# Config.net
KiCad netlist of a schematic drawn in Altium Designer
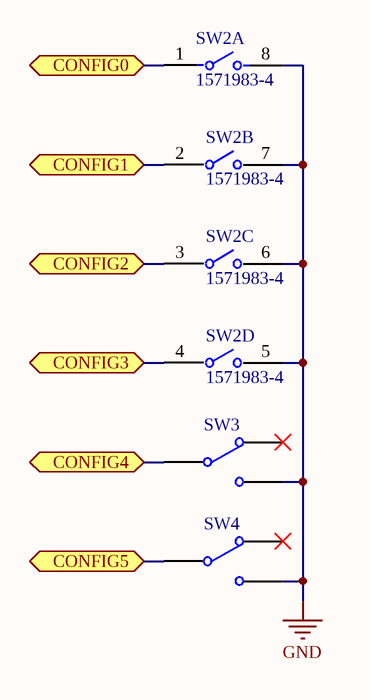
[diagram p0: Config.SchDoc]

(export (version "E")
  (design (tool "Eeschema 10.0.6"))
  (components
    (comp (ref "SW2")
      (value "1571983-4")
      (footprint "FP-1571983-4-MFG")
      (description "SWITCH SLIDE DIP SPST 25MA 24V")
      (fields
        (field (name "OCTOPART") "https://octopart.com/1571983-4-te+connectivity-46507521")
        (field (name "MANUFACTURER") "TE Connectivity")
      )
      (libsource (lib "Altium Content Vault") (part "6123b3bffd52fd60b6df23d79e332fa"))
    )
    (comp (ref "SW3")
      (value "450404015514")
      (footprint "450404015514")
      (description "450404015514 Slide Switch, 0.3A, 5Vdc, Smd Rohs Compliant: Yes")
      (libsource (lib "Altium Content Vault") (part "SPDT"))
    )
    (comp (ref "SW4")
      (value "450404015514")
      (footprint "450404015514")
      (description "450404015514 Slide Switch, 0.3A, 5Vdc, Smd Rohs Compliant: Yes")
      (libsource (lib "Altium Content Vault") (part "SPDT"))
    )
  )
  (nets
    (net (code "1") (name "/CONFIG0") (class "Default")
      (node (ref "SW2") (pin "1") (pinfunction "1_1") (pintype "passive"))
    )
    (net (code "2") (name "/CONFIG1") (class "Default")
      (node (ref "SW2") (pin "2") (pinfunction "2_2") (pintype "passive"))
    )
    (net (code "3") (name "/CONFIG2") (class "Default")
      (node (ref "SW2") (pin "3") (pinfunction "3_3") (pintype "passive"))
    )
    (net (code "4") (name "/CONFIG3") (class "Default")
      (node (ref "SW2") (pin "4") (pinfunction "4_4") (pintype "passive"))
    )
    (net (code "5") (name "/CONFIG4") (class "Default")
      (node (ref "SW3") (pin "COM") (pinfunction "COM_COM") (pintype "passive"))
    )
    (net (code "6") (name "/CONFIG5") (class "Default")
      (node (ref "SW4") (pin "COM") (pinfunction "COM_COM") (pintype "passive"))
    )
    (net (code "7") (name "GND") (class "Default")
      (node (ref "SW2") (pin "5") (pinfunction "5_5") (pintype "passive"))
      (node (ref "SW2") (pin "6") (pinfunction "6_6") (pintype "passive"))
      (node (ref "SW2") (pin "7") (pinfunction "7_7") (pintype "passive"))
      (node (ref "SW2") (pin "8") (pinfunction "8_8") (pintype "passive"))
      (node (ref "SW3") (pin "L2") (pinfunction "L2_L2") (pintype "passive"))
      (node (ref "SW4") (pin "L2") (pinfunction "L2_L2") (pintype "passive"))
    )
    (net (code "8") (name "unconnected-(SW3-PadL1)") (class "Default")
      (node (ref "SW3") (pin "L1") (pinfunction "L1_L1") (pintype "passive+no_connect"))
    )
    (net (code "9") (name "unconnected-(SW4-PadL1)") (class "Default")
      (node (ref "SW4") (pin "L1") (pinfunction "L1_L1") (pintype "passive+no_connect"))
    )
  )
)
